# GuardBunny.net
KiCad netlist of a schematic drawn in EAGLE
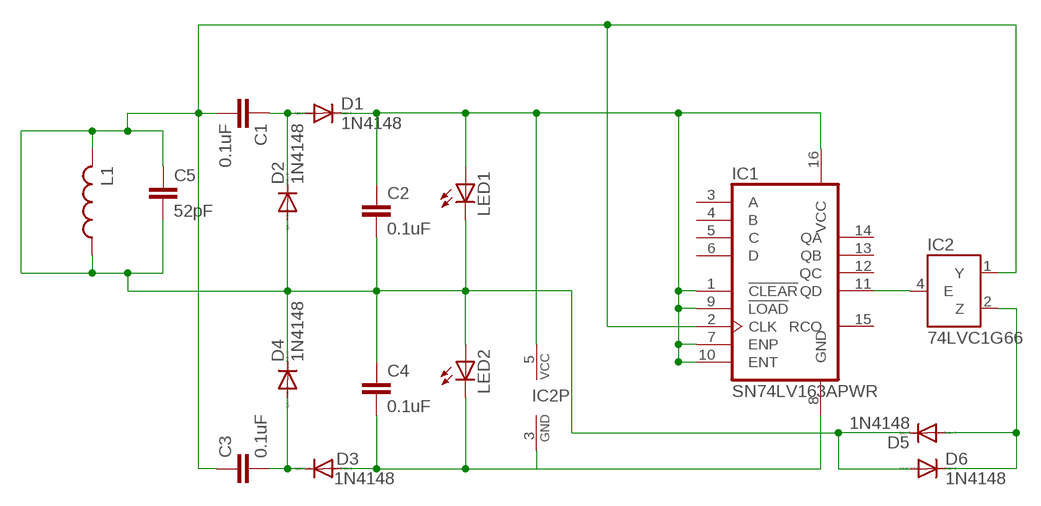
[diagram p0: schematic, sheet 1]

(export (version "E")
  (design (tool "Eeschema 10.0.6"))
  (components
    (comp (ref "C1")
      (value "0.1uF")
      (footprint "eagle-import:C0603")
      (libsource (lib "eagle-import") (part "C-EUC0603"))
    )
    (comp (ref "C2")
      (value "0.1uF")
      (footprint "eagle-import:C0603")
      (libsource (lib "eagle-import") (part "C-EUC0603"))
    )
    (comp (ref "C3")
      (value "0.1uF")
      (footprint "eagle-import:C0603")
      (libsource (lib "eagle-import") (part "C-EUC0603"))
    )
    (comp (ref "C4")
      (value "0.1uF")
      (footprint "eagle-import:C0603")
      (libsource (lib "eagle-import") (part "C-EUC0603"))
    )
    (comp (ref "C5")
      (value "52pF")
      (footprint "eagle-import:C0603")
      (libsource (lib "eagle-import") (part "C-EUC0603"))
    )
    (comp (ref "D1")
      (value "1N4148")
      (footprint "eagle-import:SOD523")
      (libsource (lib "eagle-import") (part "DIODE-SOD523"))
    )
    (comp (ref "D2")
      (value "1N4148")
      (footprint "eagle-import:SOD523")
      (libsource (lib "eagle-import") (part "DIODE-SOD523"))
    )
    (comp (ref "D3")
      (value "1N4148")
      (footprint "eagle-import:SOD523")
      (libsource (lib "eagle-import") (part "DIODE-SOD523"))
    )
    (comp (ref "D4")
      (value "1N4148")
      (footprint "eagle-import:SOD523")
      (libsource (lib "eagle-import") (part "DIODE-SOD523"))
    )
    (comp (ref "D5")
      (value "1N4148")
      (footprint "eagle-import:SOD523")
      (libsource (lib "eagle-import") (part "DIODE-SOD523"))
    )
    (comp (ref "D6")
      (value "1N4148")
      (footprint "eagle-import:SOD523")
      (libsource (lib "eagle-import") (part "DIODE-SOD523"))
    )
    (comp (ref "IC1")
      (value "SN74LV163APWR")
      (footprint "eagle-import:TSSOP16")
      (libsource (lib "eagle-import") (part "SN74LV163APWR"))
    )
    (comp (ref "IC2")
      (value "74LVC1G66")
      (footprint "eagle-import:SOT23-5")
      (libsource (lib "eagle-import") (part "741G66DBV"))
    )
    (comp (ref "L1")
      (value "L-USL2012C")
      (footprint "eagle-import:L2012C")
      (libsource (lib "eagle-import") (part "L-USL2012C"))
    )
    (comp (ref "LED1")
      (value "LEDCHIP-LED0603")
      (footprint "eagle-import:CHIP-LED0603")
      (libsource (lib "eagle-import") (part "LEDCHIP-LED0603"))
    )
    (comp (ref "LED2")
      (value "LEDCHIP-LED0603")
      (footprint "eagle-import:CHIP-LED0603")
      (libsource (lib "eagle-import") (part "LEDCHIP-LED0603"))
    )
  )
  (nets
    (net (code "1") (name "Net-(C1-Pad1)") (class "Default")
      (node (ref "C1") (pin "1") (pinfunction "1_1") (pintype "passive"))
      (node (ref "D1") (pin "A") (pinfunction "A_A") (pintype "passive"))
      (node (ref "D2") (pin "C") (pinfunction "C_C") (pintype "passive"))
    )
    (net (code "2") (name "Net-(C3-Pad2)") (class "Default")
      (node (ref "C3") (pin "2") (pinfunction "2_2") (pintype "passive"))
      (node (ref "D3") (pin "C") (pinfunction "C_C") (pintype "passive"))
      (node (ref "D4") (pin "A") (pinfunction "A_A") (pintype "passive"))
    )
    (net (code "3") (name "Net-(IC1-CLK)") (class "Default")
      (node (ref "C1") (pin "2") (pinfunction "2_2") (pintype "passive"))
      (node (ref "C2") (pin "2") (pinfunction "2_2") (pintype "passive"))
      (node (ref "C3") (pin "1") (pinfunction "1_1") (pintype "passive"))
      (node (ref "C4") (pin "1") (pinfunction "1_1") (pintype "passive"))
      (node (ref "C5") (pin "1") (pinfunction "1_1") (pintype "passive"))
      (node (ref "C5") (pin "2") (pinfunction "2_2") (pintype "passive"))
      (node (ref "D2") (pin "A") (pinfunction "A_A") (pintype "passive"))
      (node (ref "D4") (pin "C") (pinfunction "C_C") (pintype "passive"))
      (node (ref "D5") (pin "C") (pinfunction "C_C") (pintype "passive"))
      (node (ref "D6") (pin "A") (pinfunction "A_A") (pintype "passive"))
      (node (ref "IC1") (pin "2") (pinfunction "CLK_2") (pintype "input"))
      (node (ref "IC2") (pin "1") (pinfunction "Y_1") (pintype "bidirectional"))
      (node (ref "L1") (pin "1") (pinfunction "1_1") (pintype "passive"))
      (node (ref "L1") (pin "2") (pinfunction "2_2") (pintype "passive"))
      (node (ref "LED1") (pin "C") (pinfunction "C_C") (pintype "passive"))
      (node (ref "LED2") (pin "A") (pinfunction "A_A") (pintype "passive"))
    )
    (net (code "4") (name "Net-(IC1-ENP)") (class "Default")
      (node (ref "C2") (pin "1") (pinfunction "1_1") (pintype "passive"))
      (node (ref "D1") (pin "C") (pinfunction "C_C") (pintype "passive"))
      (node (ref "IC1") (pin "1") (pinfunction "~{CLEAR}_1") (pintype "input"))
      (node (ref "IC1") (pin "10") (pinfunction "ENT_10") (pintype "input"))
      (node (ref "IC1") (pin "16") (pinfunction "VCC_16") (pintype "bidirectional"))
      (node (ref "IC1") (pin "7") (pinfunction "ENP_7") (pintype "input"))
      (node (ref "IC1") (pin "9") (pinfunction "~{LOAD}_9") (pintype "input"))
      (node (ref "IC2") (pin "5") (pinfunction "VCC_5") (pintype "power_in"))
      (node (ref "LED1") (pin "A") (pinfunction "A_A") (pintype "passive"))
    )
    (net (code "5") (name "Net-(IC1-GND)") (class "Default")
      (node (ref "C4") (pin "2") (pinfunction "2_2") (pintype "passive"))
      (node (ref "D3") (pin "A") (pinfunction "A_A") (pintype "passive"))
      (node (ref "IC1") (pin "8") (pinfunction "GND_8") (pintype "bidirectional"))
      (node (ref "IC2") (pin "3") (pinfunction "GND_3") (pintype "power_in"))
      (node (ref "LED2") (pin "C") (pinfunction "C_C") (pintype "passive"))
    )
    (net (code "6") (name "Net-(IC1-QD)") (class "Default")
      (node (ref "IC1") (pin "11") (pinfunction "QD_11") (pintype "output"))
      (node (ref "IC2") (pin "4") (pinfunction "E_4") (pintype "input"))
    )
    (net (code "7") (name "Net-(IC2A-Z)") (class "Default")
      (node (ref "D5") (pin "A") (pinfunction "A_A") (pintype "passive"))
      (node (ref "D6") (pin "C") (pinfunction "C_C") (pintype "passive"))
      (node (ref "IC2") (pin "2") (pinfunction "Z_2") (pintype "bidirectional"))
    )
    (net (code "8") (name "unconnected-(IC1-A-Pad3)") (class "Default")
      (node (ref "IC1") (pin "3") (pinfunction "A_3") (pintype "input"))
    )
    (net (code "9") (name "unconnected-(IC1-B-Pad4)") (class "Default")
      (node (ref "IC1") (pin "4") (pinfunction "B_4") (pintype "input"))
    )
    (net (code "10") (name "unconnected-(IC1-C-Pad5)") (class "Default")
      (node (ref "IC1") (pin "5") (pinfunction "C_5") (pintype "input"))
    )
    (net (code "11") (name "unconnected-(IC1-D-Pad6)") (class "Default")
      (node (ref "IC1") (pin "6") (pinfunction "D_6") (pintype "input"))
    )
    (net (code "12") (name "unconnected-(IC1-QA-Pad14)") (class "Default")
      (node (ref "IC1") (pin "14") (pinfunction "QA_14") (pintype "output"))
    )
    (net (code "13") (name "unconnected-(IC1-QB-Pad13)") (class "Default")
      (node (ref "IC1") (pin "13") (pinfunction "QB_13") (pintype "output"))
    )
    (net (code "14") (name "unconnected-(IC1-QC-Pad12)") (class "Default")
      (node (ref "IC1") (pin "12") (pinfunction "QC_12") (pintype "output"))
    )
    (net (code "15") (name "unconnected-(IC1-RCO-Pad15)") (class "Default")
      (node (ref "IC1") (pin "15") (pinfunction "RCO_15") (pintype "output"))
    )
  )
)
